# BBB_Connections.net
KiCad netlist of a schematic drawn in Altium Designer
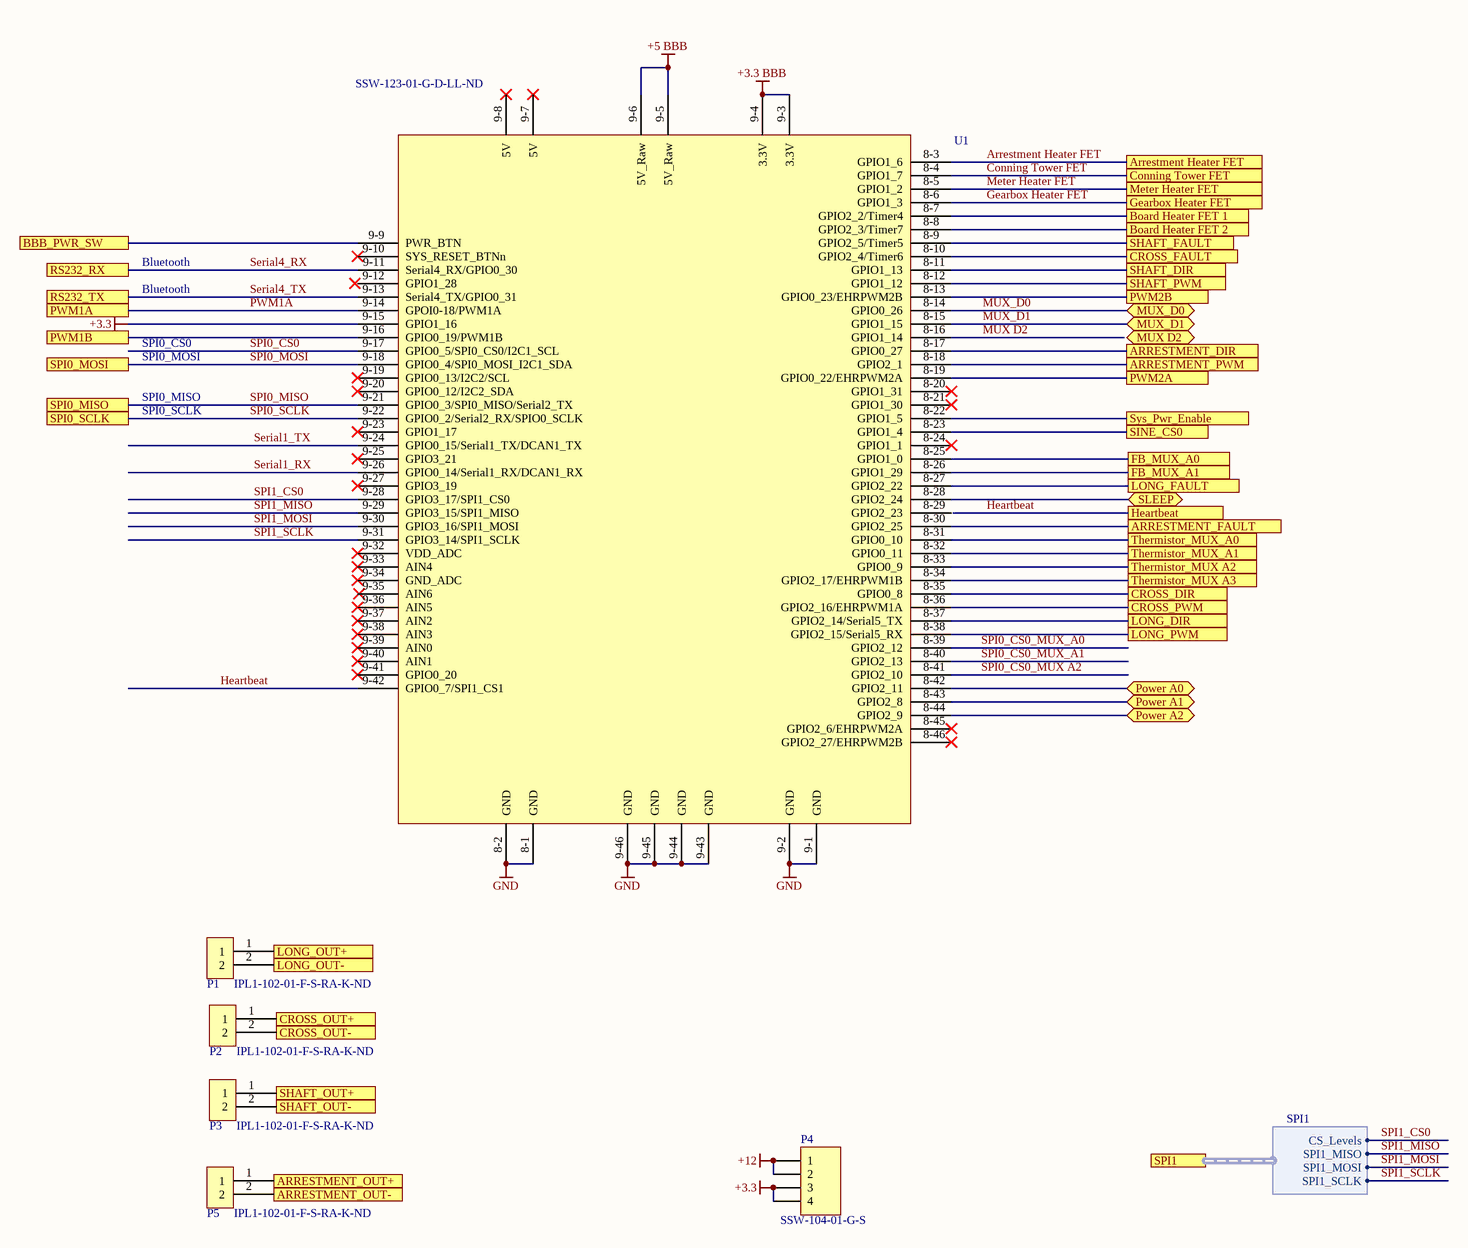
[diagram p0: BBB_Connections.SchDoc]

(export (version "E")
  (design (tool "Eeschema 10.0.6"))
  (components
    (comp (ref "P1")
      (value "IPL1-102-01-F-S-RA-K")
      (footprint "IPL1-102-01-F-S-RA-K")
      (fields
        (field (name "SUPPLIER PART NUMBER 1") "IPL1-102-01-F-S-RA-K-ND")
        (field (name "MANUFACTURER") "Samtec Inc.")
      )
      (libsource (lib "ZLS_Schematic_lib") (part "IPL1-102-01-F-S-RA-K"))
    )
    (comp (ref "P2")
      (value "IPL1-102-01-F-S-RA-K")
      (footprint "IPL1-102-01-F-S-RA-K")
      (fields
        (field (name "SUPPLIER PART NUMBER 1") "IPL1-102-01-F-S-RA-K-ND")
        (field (name "MANUFACTURER") "Samtec Inc.")
      )
      (libsource (lib "ZLS_Schematic_lib") (part "IPL1-102-01-F-S-RA-K"))
    )
    (comp (ref "P3")
      (value "IPL1-102-01-F-S-RA-K")
      (footprint "IPL1-102-01-F-S-RA-K")
      (fields
        (field (name "SUPPLIER PART NUMBER 1") "IPL1-102-01-F-S-RA-K-ND")
        (field (name "MANUFACTURER") "Samtec Inc.")
      )
      (libsource (lib "ZLS_Schematic_lib") (part "IPL1-102-01-F-S-RA-K"))
    )
    (comp (ref "P4")
      (value "SSW-104-01-G-S")
      (footprint "HDR1X4")
      (description "CONN RCPT .100\" 4POS SNGL GOLD")
      (fields (field (name "MANUFACTURER") "Samtec Inc."))
      (libsource (lib "Miscellaneous Connectors") (part "Header 4"))
    )
    (comp (ref "P5")
      (value "IPL1-102-01-F-S-RA-K")
      (footprint "IPL1-102-01-F-S-RA-K")
      (fields
        (field (name "SUPPLIER PART NUMBER 1") "IPL1-102-01-F-S-RA-K-ND")
        (field (name "MANUFACTURER") "Samtec Inc.")
      )
      (libsource (lib "ZLS_Schematic_lib") (part "IPL1-102-01-F-S-RA-K"))
    )
    (comp (ref "U1")
      (value "BBB")
      (footprint "Beaglebone Black Mezanine")
      (description "Beaglebone Black")
      (fields
        (field (name "SUPPLIER PART NUMBER 1") "SSW-123-01-G-D-LL-ND")
        (field (name "MANUFACTURER") "Samtec Inc.")
        (field (name "MANUFACTURER PART NUMBER") "SSW-123-01-G-D-LL")
      )
      (libsource (lib "ZLS_Schematic_lib") (part "Beaglebone_Black_Mezanine"))
    )
  )
  (nets
    (net (code "2") (name "+3.3") (class "Default")
      (node (ref "P4") (pin "3") (pinfunction "3_3") (pintype "passive"))
      (node (ref "P4") (pin "4") (pinfunction "4_4") (pintype "passive"))
      (node (ref "U1") (pin "9-15") (pinfunction "GPIO1_16_9-15") (pintype "passive"))
    )
    (net (code "3") (name "+3.3 BBB") (class "Default")
      (node (ref "U1") (pin "9-3") (pinfunction "3.3V_9-3") (pintype "passive"))
      (node (ref "U1") (pin "9-4") (pinfunction "3.3V_9-4") (pintype "passive"))
    )
    (net (code "4") (name "+5 BBB") (class "Default")
      (node (ref "U1") (pin "9-5") (pinfunction "5V_Raw_9-5") (pintype "passive"))
      (node (ref "U1") (pin "9-6") (pinfunction "5V_Raw_9-6") (pintype "passive"))
    )
    (net (code "5") (name "+12") (class "Default")
      (node (ref "P4") (pin "1") (pinfunction "1_1") (pintype "passive"))
      (node (ref "P4") (pin "2") (pinfunction "2_2") (pintype "passive"))
    )
    (net (code "6") (name "/ARRESTMENT_DIR") (class "Default")
      (node (ref "U1") (pin "8-17") (pinfunction "GPIO0_27_8-17") (pintype "passive"))
    )
    (net (code "7") (name "/ARRESTMENT_FAULT") (class "Default")
      (node (ref "U1") (pin "8-30") (pinfunction "GPIO2_25_8-30") (pintype "passive"))
    )
    (net (code "8") (name "/ARRESTMENT_OUT+") (class "Default")
      (node (ref "P5") (pin "1") (pinfunction "1_1") (pintype "passive"))
    )
    (net (code "9") (name "/ARRESTMENT_OUT-") (class "Default")
      (node (ref "P5") (pin "2") (pinfunction "2_2") (pintype "passive"))
    )
    (net (code "10") (name "/ARRESTMENT_PWM") (class "Default")
      (node (ref "U1") (pin "8-18") (pinfunction "GPIO2_1_8-18") (pintype "passive"))
    )
    (net (code "11") (name "/Arrestment Heater FET") (class "Default")
      (node (ref "U1") (pin "8-3") (pinfunction "GPIO1_6_8-3") (pintype "passive"))
    )
    (net (code "12") (name "/BBB_PWR_SW") (class "Default")
      (node (ref "U1") (pin "9-9") (pinfunction "PWR_BTN_9-9") (pintype "passive"))
    )
    (net (code "13") (name "/Board Heater FET 1") (class "Default")
      (node (ref "U1") (pin "8-7") (pinfunction "GPIO2_2/Timer4_8-7") (pintype "passive"))
    )
    (net (code "14") (name "/Board Heater FET 2") (class "Default")
      (node (ref "U1") (pin "8-8") (pinfunction "GPIO2_3/Timer7_8-8") (pintype "passive"))
    )
    (net (code "15") (name "/CROSS_DIR") (class "Default")
      (node (ref "U1") (pin "8-35") (pinfunction "GPIO0_8_8-35") (pintype "passive"))
    )
    (net (code "16") (name "/CROSS_FAULT") (class "Default")
      (node (ref "U1") (pin "8-10") (pinfunction "GPIO2_4/Timer6_8-10") (pintype "passive"))
    )
    (net (code "17") (name "/CROSS_OUT+") (class "Default")
      (node (ref "P2") (pin "1") (pinfunction "1_1") (pintype "passive"))
    )
    (net (code "18") (name "/CROSS_OUT-") (class "Default")
      (node (ref "P2") (pin "2") (pinfunction "2_2") (pintype "passive"))
    )
    (net (code "19") (name "/CROSS_PWM") (class "Default")
      (node (ref "U1") (pin "8-36") (pinfunction "GPIO2_16/EHRPWM1A_8-36") (pintype "passive"))
    )
    (net (code "20") (name "/Conning Tower FET") (class "Default")
      (node (ref "U1") (pin "8-4") (pinfunction "GPIO1_7_8-4") (pintype "passive"))
    )
    (net (code "21") (name "/FB_MUX_A0") (class "Default")
      (node (ref "U1") (pin "8-25") (pinfunction "GPIO1_0_8-25") (pintype "passive"))
    )
    (net (code "22") (name "/FB_MUX_A1") (class "Default")
      (node (ref "U1") (pin "8-26") (pinfunction "GPIO1_29_8-26") (pintype "passive"))
    )
    (net (code "23") (name "/Gearbox Heater FET") (class "Default")
      (node (ref "U1") (pin "8-6") (pinfunction "GPIO1_3_8-6") (pintype "passive"))
    )
    (net (code "24") (name "/Heartbeat") (class "Default")
      (node (ref "U1") (pin "9-42") (pinfunction "GPIO0_7/SPI1_CS1_9-42") (pintype "passive"))
    )
    (net (code "25") (name "/LONG_DIR") (class "Default")
      (node (ref "U1") (pin "8-37") (pinfunction "GPIO2_14/Serial5_TX_8-37") (pintype "passive"))
    )
    (net (code "26") (name "/LONG_FAULT") (class "Default")
      (node (ref "U1") (pin "8-27") (pinfunction "GPIO2_22_8-27") (pintype "passive"))
    )
    (net (code "27") (name "/LONG_OUT+") (class "Default")
      (node (ref "P1") (pin "1") (pinfunction "1_1") (pintype "passive"))
    )
    (net (code "28") (name "/LONG_OUT-") (class "Default")
      (node (ref "P1") (pin "2") (pinfunction "2_2") (pintype "passive"))
    )
    (net (code "29") (name "/LONG_PWM") (class "Default")
      (node (ref "U1") (pin "8-38") (pinfunction "GPIO2_15/Serial5_RX_8-38") (pintype "passive"))
    )
    (net (code "30") (name "/MUX D2") (class "Default")
      (node (ref "U1") (pin "8-16") (pinfunction "GPIO1_14_8-16") (pintype "passive"))
    )
    (net (code "31") (name "/MUX_D0") (class "Default")
      (node (ref "U1") (pin "8-14") (pinfunction "GPIO0_26_8-14") (pintype "passive"))
    )
    (net (code "32") (name "/MUX_D1") (class "Default")
      (node (ref "U1") (pin "8-15") (pinfunction "GPIO1_15_8-15") (pintype "passive"))
    )
    (net (code "33") (name "/Meter Heater FET") (class "Default")
      (node (ref "U1") (pin "8-5") (pinfunction "GPIO1_2_8-5") (pintype "passive"))
    )
    (net (code "34") (name "/PWM1A") (class "Default")
      (node (ref "U1") (pin "9-14") (pinfunction "GPOI0-18/PWM1A_9-14") (pintype "passive"))
    )
    (net (code "35") (name "/PWM1B") (class "Default")
      (node (ref "U1") (pin "9-16") (pinfunction "GPIO0_19/PWM1B_9-16") (pintype "passive"))
    )
    (net (code "36") (name "/PWM2A") (class "Default")
      (node (ref "U1") (pin "8-19") (pinfunction "GPIO0_22/EHRPWM2A_8-19") (pintype "passive"))
    )
    (net (code "37") (name "/PWM2B") (class "Default")
      (node (ref "U1") (pin "8-13") (pinfunction "GPIO0_23/EHRPWM2B_8-13") (pintype "passive"))
    )
    (net (code "38") (name "/Power A0") (class "Default")
      (node (ref "U1") (pin "8-42") (pinfunction "GPIO2_11_8-42") (pintype "passive"))
    )
    (net (code "39") (name "/Power A1") (class "Default")
      (node (ref "U1") (pin "8-43") (pinfunction "GPIO2_8_8-43") (pintype "passive"))
    )
    (net (code "40") (name "/Power A2") (class "Default")
      (node (ref "U1") (pin "8-44") (pinfunction "GPIO2_9_8-44") (pintype "passive"))
    )
    (net (code "41") (name "/SHAFT_DIR") (class "Default")
      (node (ref "U1") (pin "8-11") (pinfunction "GPIO1_13_8-11") (pintype "passive"))
    )
    (net (code "42") (name "/SHAFT_FAULT") (class "Default")
      (node (ref "U1") (pin "8-9") (pinfunction "GPIO2_5/Timer5_8-9") (pintype "passive"))
    )
    (net (code "43") (name "/SHAFT_OUT+") (class "Default")
      (node (ref "P3") (pin "1") (pinfunction "1_1") (pintype "passive"))
    )
    (net (code "44") (name "/SHAFT_OUT-") (class "Default")
      (node (ref "P3") (pin "2") (pinfunction "2_2") (pintype "passive"))
    )
    (net (code "45") (name "/SHAFT_PWM") (class "Default")
      (node (ref "U1") (pin "8-12") (pinfunction "GPIO1_12_8-12") (pintype "passive"))
    )
    (net (code "46") (name "/SINE_CS0") (class "Default")
      (node (ref "U1") (pin "8-23") (pinfunction "GPIO1_4_8-23") (pintype "passive"))
    )
    (net (code "47") (name "/SLEEP") (class "Default")
      (node (ref "U1") (pin "8-28") (pinfunction "GPIO2_24_8-28") (pintype "passive"))
    )
    (net (code "48") (name "/SPI0_CS0") (class "Default")
      (node (ref "U1") (pin "9-17") (pinfunction "GPIO0_5/SPI0_CS0/I2C1_SCL_9-17") (pintype "passive"))
    )
    (net (code "49") (name "/SPI0_CS0_MUX A2") (class "Default")
      (node (ref "U1") (pin "8-41") (pinfunction "GPIO2_10_8-41") (pintype "passive"))
    )
    (net (code "50") (name "/SPI0_CS0_MUX_A0") (class "Default")
      (node (ref "U1") (pin "8-39") (pinfunction "GPIO2_12_8-39") (pintype "passive"))
    )
    (net (code "51") (name "/SPI0_CS0_MUX_A1") (class "Default")
      (node (ref "U1") (pin "8-40") (pinfunction "GPIO2_13_8-40") (pintype "passive"))
    )
    (net (code "52") (name "/SPI0_MISO") (class "Default")
      (node (ref "U1") (pin "9-21") (pinfunction "GPIO0_3/SPI0_MISO/Serial2_TX_9-21") (pintype "passive"))
    )
    (net (code "53") (name "/SPI0_MOSI") (class "Default")
      (node (ref "U1") (pin "9-18") (pinfunction "GPIO0_4/SPI0_MOSI_I2C1_SDA_9-18") (pintype "passive"))
    )
    (net (code "54") (name "/SPI0_SCLK") (class "Default")
      (node (ref "U1") (pin "9-22") (pinfunction "GPIO0_2/Serial2_RX/SPIO0_SCLK_9-22") (pintype "passive"))
    )
    (net (code "55") (name "/SPI1_CS0") (class "Default")
      (node (ref "U1") (pin "9-28") (pinfunction "GPIO3_17/SPI1_CS0_9-28") (pintype "passive"))
    )
    (net (code "56") (name "/SPI1_MISO") (class "Default")
      (node (ref "U1") (pin "9-29") (pinfunction "GPIO3_15/SPI1_MISO_9-29") (pintype "passive"))
    )
    (net (code "57") (name "/SPI1_MOSI") (class "Default")
      (node (ref "U1") (pin "9-30") (pinfunction "GPIO3_16/SPI1_MOSI_9-30") (pintype "passive"))
    )
    (net (code "58") (name "/SPI1_SCLK") (class "Default")
      (node (ref "U1") (pin "9-31") (pinfunction "GPIO3_14/SPI1_SCLK_9-31") (pintype "passive"))
    )
    (net (code "59") (name "/Serial1_RX") (class "Default")
      (node (ref "U1") (pin "9-26") (pinfunction "GPIO0_14/Serial1_RX/DCAN1_RX_9-26") (pintype "passive"))
    )
    (net (code "60") (name "/Serial1_TX") (class "Default")
      (node (ref "U1") (pin "9-24") (pinfunction "GPIO0_15/Serial1_TX/DCAN1_TX_9-24") (pintype "passive"))
    )
    (net (code "61") (name "/Serial4_RX") (class "Default")
      (node (ref "U1") (pin "9-11") (pinfunction "Serial4_RX/GPIO0_30_9-11") (pintype "passive"))
    )
    (net (code "62") (name "/Serial4_TX") (class "Default")
      (node (ref "U1") (pin "9-13") (pinfunction "Serial4_TX/GPIO0_31_9-13") (pintype "passive"))
    )
    (net (code "63") (name "/Sys_Pwr_Enable") (class "Default")
      (node (ref "U1") (pin "8-22") (pinfunction "GPIO1_5_8-22") (pintype "passive"))
    )
    (net (code "64") (name "/Thermistor_MUX A2") (class "Default")
      (node (ref "U1") (pin "8-33") (pinfunction "GPIO0_9_8-33") (pintype "passive"))
    )
    (net (code "65") (name "/Thermistor_MUX A3") (class "Default")
      (node (ref "U1") (pin "8-34") (pinfunction "GPIO2_17/EHRPWM1B_8-34") (pintype "passive"))
    )
    (net (code "66") (name "/Thermistor_MUX_A0") (class "Default")
      (node (ref "U1") (pin "8-31") (pinfunction "GPIO0_10_8-31") (pintype "passive"))
    )
    (net (code "67") (name "/Thermistor_MUX_A1") (class "Default")
      (node (ref "U1") (pin "8-32") (pinfunction "GPIO0_11_8-32") (pintype "passive"))
    )
    (net (code "69") (name "GND") (class "Default")
      (node (ref "U1") (pin "8-1") (pinfunction "GND_8-1") (pintype "passive"))
      (node (ref "U1") (pin "8-2") (pinfunction "GND_8-2") (pintype "passive"))
      (node (ref "U1") (pin "9-1") (pinfunction "GND_9-1") (pintype "passive"))
      (node (ref "U1") (pin "9-2") (pinfunction "GND_9-2") (pintype "passive"))
      (node (ref "U1") (pin "9-43") (pinfunction "GND_9-43") (pintype "passive"))
      (node (ref "U1") (pin "9-44") (pinfunction "GND_9-44") (pintype "passive"))
      (node (ref "U1") (pin "9-45") (pinfunction "GND_9-45") (pintype "passive"))
      (node (ref "U1") (pin "9-46") (pinfunction "GND_9-46") (pintype "passive"))
    )
    (net (code "70") (name "unconnected-(U1-5V-Pad9-7)") (class "Default")
      (node (ref "U1") (pin "9-7") (pinfunction "5V_9-7") (pintype "passive+no_connect"))
    )
    (net (code "71") (name "unconnected-(U1-5V-Pad9-8)") (class "Default")
      (node (ref "U1") (pin "9-8") (pinfunction "5V_9-8") (pintype "passive+no_connect"))
    )
    (net (code "72") (name "unconnected-(U1-AIN0-Pad9-39)") (class "Default")
      (node (ref "U1") (pin "9-39") (pinfunction "AIN0_9-39") (pintype "passive+no_connect"))
    )
    (net (code "73") (name "unconnected-(U1-AIN1-Pad9-40)") (class "Default")
      (node (ref "U1") (pin "9-40") (pinfunction "AIN1_9-40") (pintype "passive+no_connect"))
    )
    (net (code "74") (name "unconnected-(U1-AIN2-Pad9-37)") (class "Default")
      (node (ref "U1") (pin "9-37") (pinfunction "AIN2_9-37") (pintype "passive+no_connect"))
    )
    (net (code "75") (name "unconnected-(U1-AIN3-Pad9-38)") (class "Default")
      (node (ref "U1") (pin "9-38") (pinfunction "AIN3_9-38") (pintype "passive+no_connect"))
    )
    (net (code "76") (name "unconnected-(U1-AIN4-Pad9-33)") (class "Default")
      (node (ref "U1") (pin "9-33") (pinfunction "AIN4_9-33") (pintype "passive+no_connect"))
    )
    (net (code "77") (name "unconnected-(U1-AIN5-Pad9-36)") (class "Default")
      (node (ref "U1") (pin "9-36") (pinfunction "AIN5_9-36") (pintype "passive+no_connect"))
    )
    (net (code "78") (name "unconnected-(U1-AIN6-Pad9-35)") (class "Default")
      (node (ref "U1") (pin "9-35") (pinfunction "AIN6_9-35") (pintype "passive"))
    )
    (net (code "79") (name "unconnected-(U1-GND_ADC-Pad9-34)") (class "Default")
      (node (ref "U1") (pin "9-34") (pinfunction "GND_ADC_9-34") (pintype "passive+no_connect"))
    )
    (net (code "80") (name "unconnected-(U1-GPIO0_12{slash}I2C2_SDA-Pad9-20)") (class "Default")
      (node (ref "U1") (pin "9-20") (pinfunction "GPIO0_12/I2C2_SDA_9-20") (pintype "passive+no_connect"))
    )
    (net (code "81") (name "unconnected-(U1-GPIO0_13{slash}I2C2{slash}SCL-Pad9-19)") (class "Default")
      (node (ref "U1") (pin "9-19") (pinfunction "GPIO0_13/I2C2/SCL_9-19") (pintype "passive+no_connect"))
    )
    (net (code "82") (name "unconnected-(U1-GPIO0_20-Pad9-41)") (class "Default")
      (node (ref "U1") (pin "9-41") (pinfunction "GPIO0_20_9-41") (pintype "passive+no_connect"))
    )
    (net (code "83") (name "unconnected-(U1-GPIO1_1-Pad8-24)") (class "Default")
      (node (ref "U1") (pin "8-24") (pinfunction "GPIO1_1_8-24") (pintype "passive+no_connect"))
    )
    (net (code "84") (name "unconnected-(U1-GPIO1_17-Pad9-23)") (class "Default")
      (node (ref "U1") (pin "9-23") (pinfunction "GPIO1_17_9-23") (pintype "passive+no_connect"))
    )
    (net (code "85") (name "unconnected-(U1-GPIO1_28-Pad9-12)") (class "Default")
      (node (ref "U1") (pin "9-12") (pinfunction "GPIO1_28_9-12") (pintype "passive"))
    )
    (net (code "86") (name "unconnected-(U1-GPIO1_30-Pad8-21)") (class "Default")
      (node (ref "U1") (pin "8-21") (pinfunction "GPIO1_30_8-21") (pintype "passive+no_connect"))
    )
    (net (code "87") (name "unconnected-(U1-GPIO1_31-Pad8-20)") (class "Default")
      (node (ref "U1") (pin "8-20") (pinfunction "GPIO1_31_8-20") (pintype "passive+no_connect"))
    )
    (net (code "88") (name "unconnected-(U1-GPIO2_6{slash}EHRPWM2A-Pad8-45)") (class "Default")
      (node (ref "U1") (pin "8-45") (pinfunction "GPIO2_6/EHRPWM2A_8-45") (pintype "passive+no_connect"))
    )
    (net (code "89") (name "unconnected-(U1-GPIO2_23-Pad8-29)") (class "Default")
      (node (ref "U1") (pin "8-29") (pinfunction "GPIO2_23_8-29") (pintype "passive"))
    )
    (net (code "90") (name "unconnected-(U1-GPIO2_27{slash}EHRPWM2B-Pad8-46)") (class "Default")
      (node (ref "U1") (pin "8-46") (pinfunction "GPIO2_27/EHRPWM2B_8-46") (pintype "passive+no_connect"))
    )
    (net (code "91") (name "unconnected-(U1-GPIO3_19-Pad9-27)") (class "Default")
      (node (ref "U1") (pin "9-27") (pinfunction "GPIO3_19_9-27") (pintype "passive+no_connect"))
    )
    (net (code "92") (name "unconnected-(U1-GPIO3_21-Pad9-25)") (class "Default")
      (node (ref "U1") (pin "9-25") (pinfunction "GPIO3_21_9-25") (pintype "passive+no_connect"))
    )
    (net (code "93") (name "unconnected-(U1-SYS_RESET_BTNn-Pad9-10)") (class "Default")
      (node (ref "U1") (pin "9-10") (pinfunction "SYS_RESET_BTNn_9-10") (pintype "passive+no_connect"))
    )
    (net (code "94") (name "unconnected-(U1-VDD_ADC-Pad9-32)") (class "Default")
      (node (ref "U1") (pin "9-32") (pinfunction "VDD_ADC_9-32") (pintype "passive+no_connect"))
    )
  )
)
